# Power.net
KiCad netlist of a schematic drawn in Altium Designer
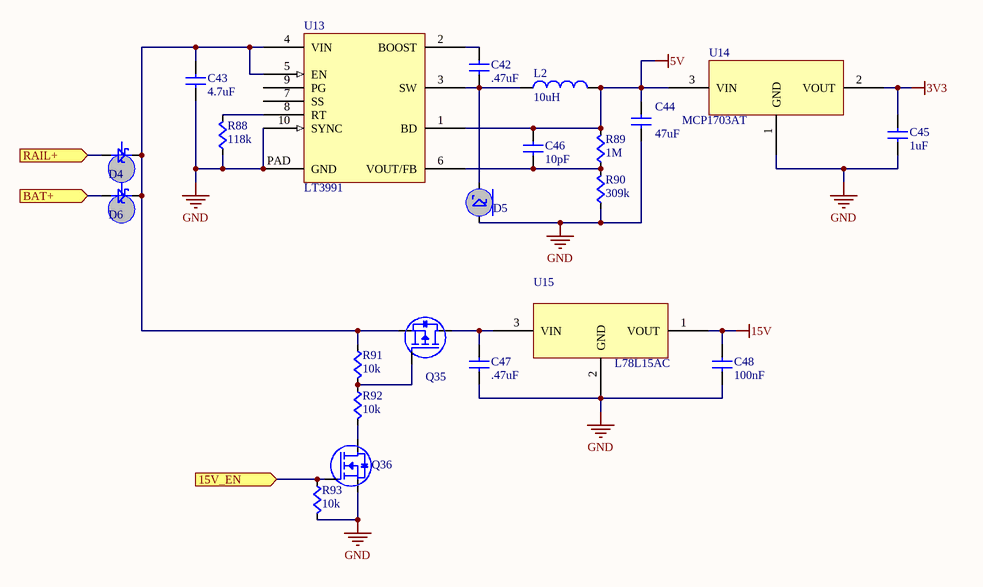
[diagram p0: Power.SchDoc]

(export (version "E")
  (design (tool "Eeschema 10.0.6"))
  (components
    (comp (ref "C42")
      (value ".47uF")
      (footprint "CAPC0603")
      (fields (field (name "Comment") "Cap"))
      (libsource (lib "SubjuGator8") (part "Cap"))
    )
    (comp (ref "C43")
      (value "4.7uF")
      (footprint "CAPC0805")
      (fields (field (name "Comment") "Cap"))
      (libsource (lib "SubjuGator8") (part "Cap"))
    )
    (comp (ref "C44")
      (value "47uF")
      (footprint "CAPC1206")
      (fields (field (name "Comment") "Cap"))
      (libsource (lib "SubjuGator8") (part "Cap"))
    )
    (comp (ref "C45")
      (value "1uF")
      (footprint "CAPC0603")
      (fields (field (name "Comment") "Cap"))
      (libsource (lib "SubjuGator8") (part "Cap"))
    )
    (comp (ref "C46")
      (value "10pF")
      (footprint "CAPC0603")
      (fields (field (name "Comment") "Cap"))
      (libsource (lib "SubjuGator8") (part "Cap"))
    )
    (comp (ref "C47")
      (value ".47uF")
      (footprint "CAPC0603")
      (fields (field (name "Comment") "Cap"))
      (libsource (lib "SubjuGator8") (part "Cap"))
    )
    (comp (ref "C48")
      (value "100nF")
      (footprint "CAPC0603")
      (fields (field (name "Comment") "Cap"))
      (libsource (lib "SubjuGator8") (part "Cap"))
    )
    (comp (ref "D4")
      (value "DFLS160")
      (footprint "POWERDI123")
      (description "1.0A Surface Mount Schottky Barrier Rectifier")
      (libsource (lib "SubjuGator8") (part "DFLS160"))
    )
    (comp (ref "D5")
      (value "DFLS160")
      (footprint "POWERDI123")
      (description "1.0A Surface Mount Schottky Barrier Rectifier")
      (libsource (lib "") (part "DFLS160_1"))
    )
    (comp (ref "D6")
      (value "DFLS160")
      (footprint "POWERDI123")
      (description "1.0A Surface Mount Schottky Barrier Rectifier")
      (libsource (lib "SubjuGator8") (part "DFLS160"))
    )
    (comp (ref "L2")
      (value "Inductor")
      (footprint "CDPH4D19F")
      (fields (field (name "INDUCTANCE") "10uH"))
      (libsource (lib "SubjuGator8") (part "Inductor"))
    )
    (comp (ref "Q35")
      (value "FDN5618P")
      (footprint "PowerSOT-3")
      (description "60V P-Channel Logic Level PowerTrench MOSFET")
      (libsource (lib "SubjuGator8") (part "FDN5618P"))
    )
    (comp (ref "Q36")
      (value "FDN5630")
      (footprint "PowerSOT-3")
      (description "60V N-Channel PowerTrench MOSFET")
      (libsource (lib "SubjuGator8") (part "FDN5630"))
    )
    (comp (ref "R88")
      (value "118k")
      (footprint "RES0603")
      (fields (field (name "Comment") "Res"))
      (libsource (lib "SubjuGator8") (part "Res"))
    )
    (comp (ref "R89")
      (value "1M")
      (footprint "RES0603")
      (fields (field (name "Comment") "Res"))
      (libsource (lib "SubjuGator8") (part "Res"))
    )
    (comp (ref "R90")
      (value "309k")
      (footprint "RES0603")
      (fields (field (name "Comment") "Res"))
      (libsource (lib "SubjuGator8") (part "Res"))
    )
    (comp (ref "R91")
      (value "10k")
      (footprint "RES0603")
      (fields (field (name "Comment") "Res"))
      (libsource (lib "SubjuGator8") (part "Res"))
    )
    (comp (ref "R92")
      (value "10k")
      (footprint "RES0603")
      (fields (field (name "Comment") "Res"))
      (libsource (lib "SubjuGator8") (part "Res"))
    )
    (comp (ref "R93")
      (value "10k")
      (footprint "RES0603")
      (fields (field (name "Comment") "Res"))
      (libsource (lib "SubjuGator8") (part "Res"))
    )
    (comp (ref "U13")
      (value "LT3991")
      (footprint "LTS3991MSE")
      (description "55V, 1.2A Step-Down Regulator with 2.8uA Quiescent Current")
      (libsource (lib "SubjuGator8") (part "LT3991"))
    )
    (comp (ref "U14")
      (value "MCP1703AT")
      (footprint "MCP1703AT-xx02EMB")
      (description "250 mA, 16V, Low Quiescent Current LDO Regulator")
      (libsource (lib "SubjuGator8") (part "MCP1703AT"))
    )
    (comp (ref "U15")
      (value "L78L15AC")
      (footprint "L78LxxAxUTR")
      (description "Positive Voltage Regulator")
      (libsource (lib "SubjuGator8") (part "L78LxxAx"))
    )
  )
  (nets
    (net (code "1") (name "/15V_EN") (class "Default")
      (node (ref "Q36") (pin "G") (pinfunction "G_G") (pintype "passive"))
      (node (ref "R93") (pin "1") (pinfunction "A_1") (pintype "passive"))
    )
    (net (code "2") (name "/BAT+") (class "Default")
      (node (ref "D6") (pin "A") (pinfunction "A_A") (pintype "passive"))
    )
    (net (code "3") (name "/RAIL+") (class "Default")
      (node (ref "D4") (pin "A") (pinfunction "A_A") (pintype "passive"))
    )
    (net (code "4") (name "3V3") (class "Default")
      (node (ref "C45") (pin "1") (pinfunction "A_1") (pintype "passive"))
      (node (ref "U14") (pin "2") (pinfunction "VOUT_2") (pintype "passive"))
    )
    (net (code "5") (name "5V") (class "Default")
      (node (ref "C44") (pin "1") (pinfunction "A_1") (pintype "passive"))
      (node (ref "C46") (pin "2") (pinfunction "B_2") (pintype "passive"))
      (node (ref "L2") (pin "2") (pinfunction "B_2") (pintype "passive"))
      (node (ref "R89") (pin "1") (pinfunction "A_1") (pintype "passive"))
      (node (ref "U13") (pin "1") (pinfunction "BD_1") (pintype "passive"))
      (node (ref "U14") (pin "3") (pinfunction "VIN_3") (pintype "passive"))
    )
    (net (code "6") (name "15V") (class "Default")
      (node (ref "C48") (pin "1") (pinfunction "A_1") (pintype "passive"))
      (node (ref "U15") (pin "1") (pinfunction "VOUT_1") (pintype "passive"))
    )
    (net (code "7") (name "GND") (class "Default")
      (node (ref "C43") (pin "2") (pinfunction "B_2") (pintype "passive"))
      (node (ref "C44") (pin "2") (pinfunction "B_2") (pintype "passive"))
      (node (ref "C45") (pin "2") (pinfunction "B_2") (pintype "passive"))
      (node (ref "C47") (pin "2") (pinfunction "B_2") (pintype "passive"))
      (node (ref "C48") (pin "2") (pinfunction "B_2") (pintype "passive"))
      (node (ref "D5") (pin "A") (pinfunction "A_A") (pintype "passive"))
      (node (ref "Q36") (pin "S") (pinfunction "S_S") (pintype "passive"))
      (node (ref "R88") (pin "2") (pinfunction "B_2") (pintype "passive"))
      (node (ref "R90") (pin "2") (pinfunction "B_2") (pintype "passive"))
      (node (ref "R93") (pin "2") (pinfunction "B_2") (pintype "passive"))
      (node (ref "U13") (pin "10") (pinfunction "SYNC_10") (pintype "input"))
      (node (ref "U13") (pin "PAD") (pinfunction "GND_PAD") (pintype "passive"))
      (node (ref "U14") (pin "1") (pinfunction "GND_1") (pintype "power_in"))
      (node (ref "U15") (pin "2") (pinfunction "GND_2") (pintype "power_in"))
    )
    (net (code "8") (name "Net-(C42-A)") (class "Default")
      (node (ref "C42") (pin "1") (pinfunction "A_1") (pintype "passive"))
      (node (ref "U13") (pin "2") (pinfunction "BOOST_2") (pintype "passive"))
    )
    (net (code "9") (name "Net-(C42-B)") (class "Default")
      (node (ref "C42") (pin "2") (pinfunction "B_2") (pintype "passive"))
      (node (ref "D5") (pin "C") (pinfunction "C_C") (pintype "passive"))
      (node (ref "L2") (pin "1") (pinfunction "A_1") (pintype "passive"))
      (node (ref "U13") (pin "3") (pinfunction "SW_3") (pintype "passive"))
    )
    (net (code "10") (name "Net-(C43-A)") (class "Default")
      (node (ref "C43") (pin "1") (pinfunction "A_1") (pintype "passive"))
      (node (ref "D4") (pin "C") (pinfunction "C_C") (pintype "passive"))
      (node (ref "D6") (pin "C") (pinfunction "C_C") (pintype "passive"))
      (node (ref "Q35") (pin "S") (pinfunction "S_S") (pintype "passive"))
      (node (ref "R91") (pin "2") (pinfunction "B_2") (pintype "passive"))
      (node (ref "U13") (pin "4") (pinfunction "VIN_4") (pintype "power_in"))
      (node (ref "U13") (pin "5") (pinfunction "EN_5") (pintype "input"))
    )
    (net (code "11") (name "Net-(C46-A)") (class "Default")
      (node (ref "C46") (pin "1") (pinfunction "A_1") (pintype "passive"))
      (node (ref "R89") (pin "2") (pinfunction "B_2") (pintype "passive"))
      (node (ref "R90") (pin "1") (pinfunction "A_1") (pintype "passive"))
      (node (ref "U13") (pin "6") (pinfunction "VOUT/FB_6") (pintype "passive"))
    )
    (net (code "12") (name "Net-(C47-A)") (class "Default")
      (node (ref "C47") (pin "1") (pinfunction "A_1") (pintype "passive"))
      (node (ref "Q35") (pin "D") (pinfunction "D_D") (pintype "passive"))
      (node (ref "U15") (pin "3") (pinfunction "VIN_3") (pintype "passive"))
    )
    (net (code "13") (name "Net-(R88-A)") (class "Default")
      (node (ref "R88") (pin "1") (pinfunction "A_1") (pintype "passive"))
      (node (ref "U13") (pin "8") (pinfunction "RT_8") (pintype "passive"))
    )
    (net (code "14") (name "Net-(R91-A)") (class "Default")
      (node (ref "Q35") (pin "G") (pinfunction "G_G") (pintype "passive"))
      (node (ref "R91") (pin "1") (pinfunction "A_1") (pintype "passive"))
      (node (ref "R92") (pin "2") (pinfunction "B_2") (pintype "passive"))
    )
    (net (code "15") (name "Net-(R92-A)") (class "Default")
      (node (ref "Q36") (pin "D") (pinfunction "D_D") (pintype "passive"))
      (node (ref "R92") (pin "1") (pinfunction "A_1") (pintype "passive"))
    )
    (net (code "16") (name "unconnected-(U13-PG-Pad9)") (class "Default")
      (node (ref "U13") (pin "9") (pinfunction "PG_9") (pintype "open_collector"))
    )
    (net (code "17") (name "unconnected-(U13-SS-Pad7)") (class "Default")
      (node (ref "U13") (pin "7") (pinfunction "SS_7") (pintype "passive"))
    )
  )
)
